# design.net
KiCad netlist of a schematic drawn in EasyEDA Pro
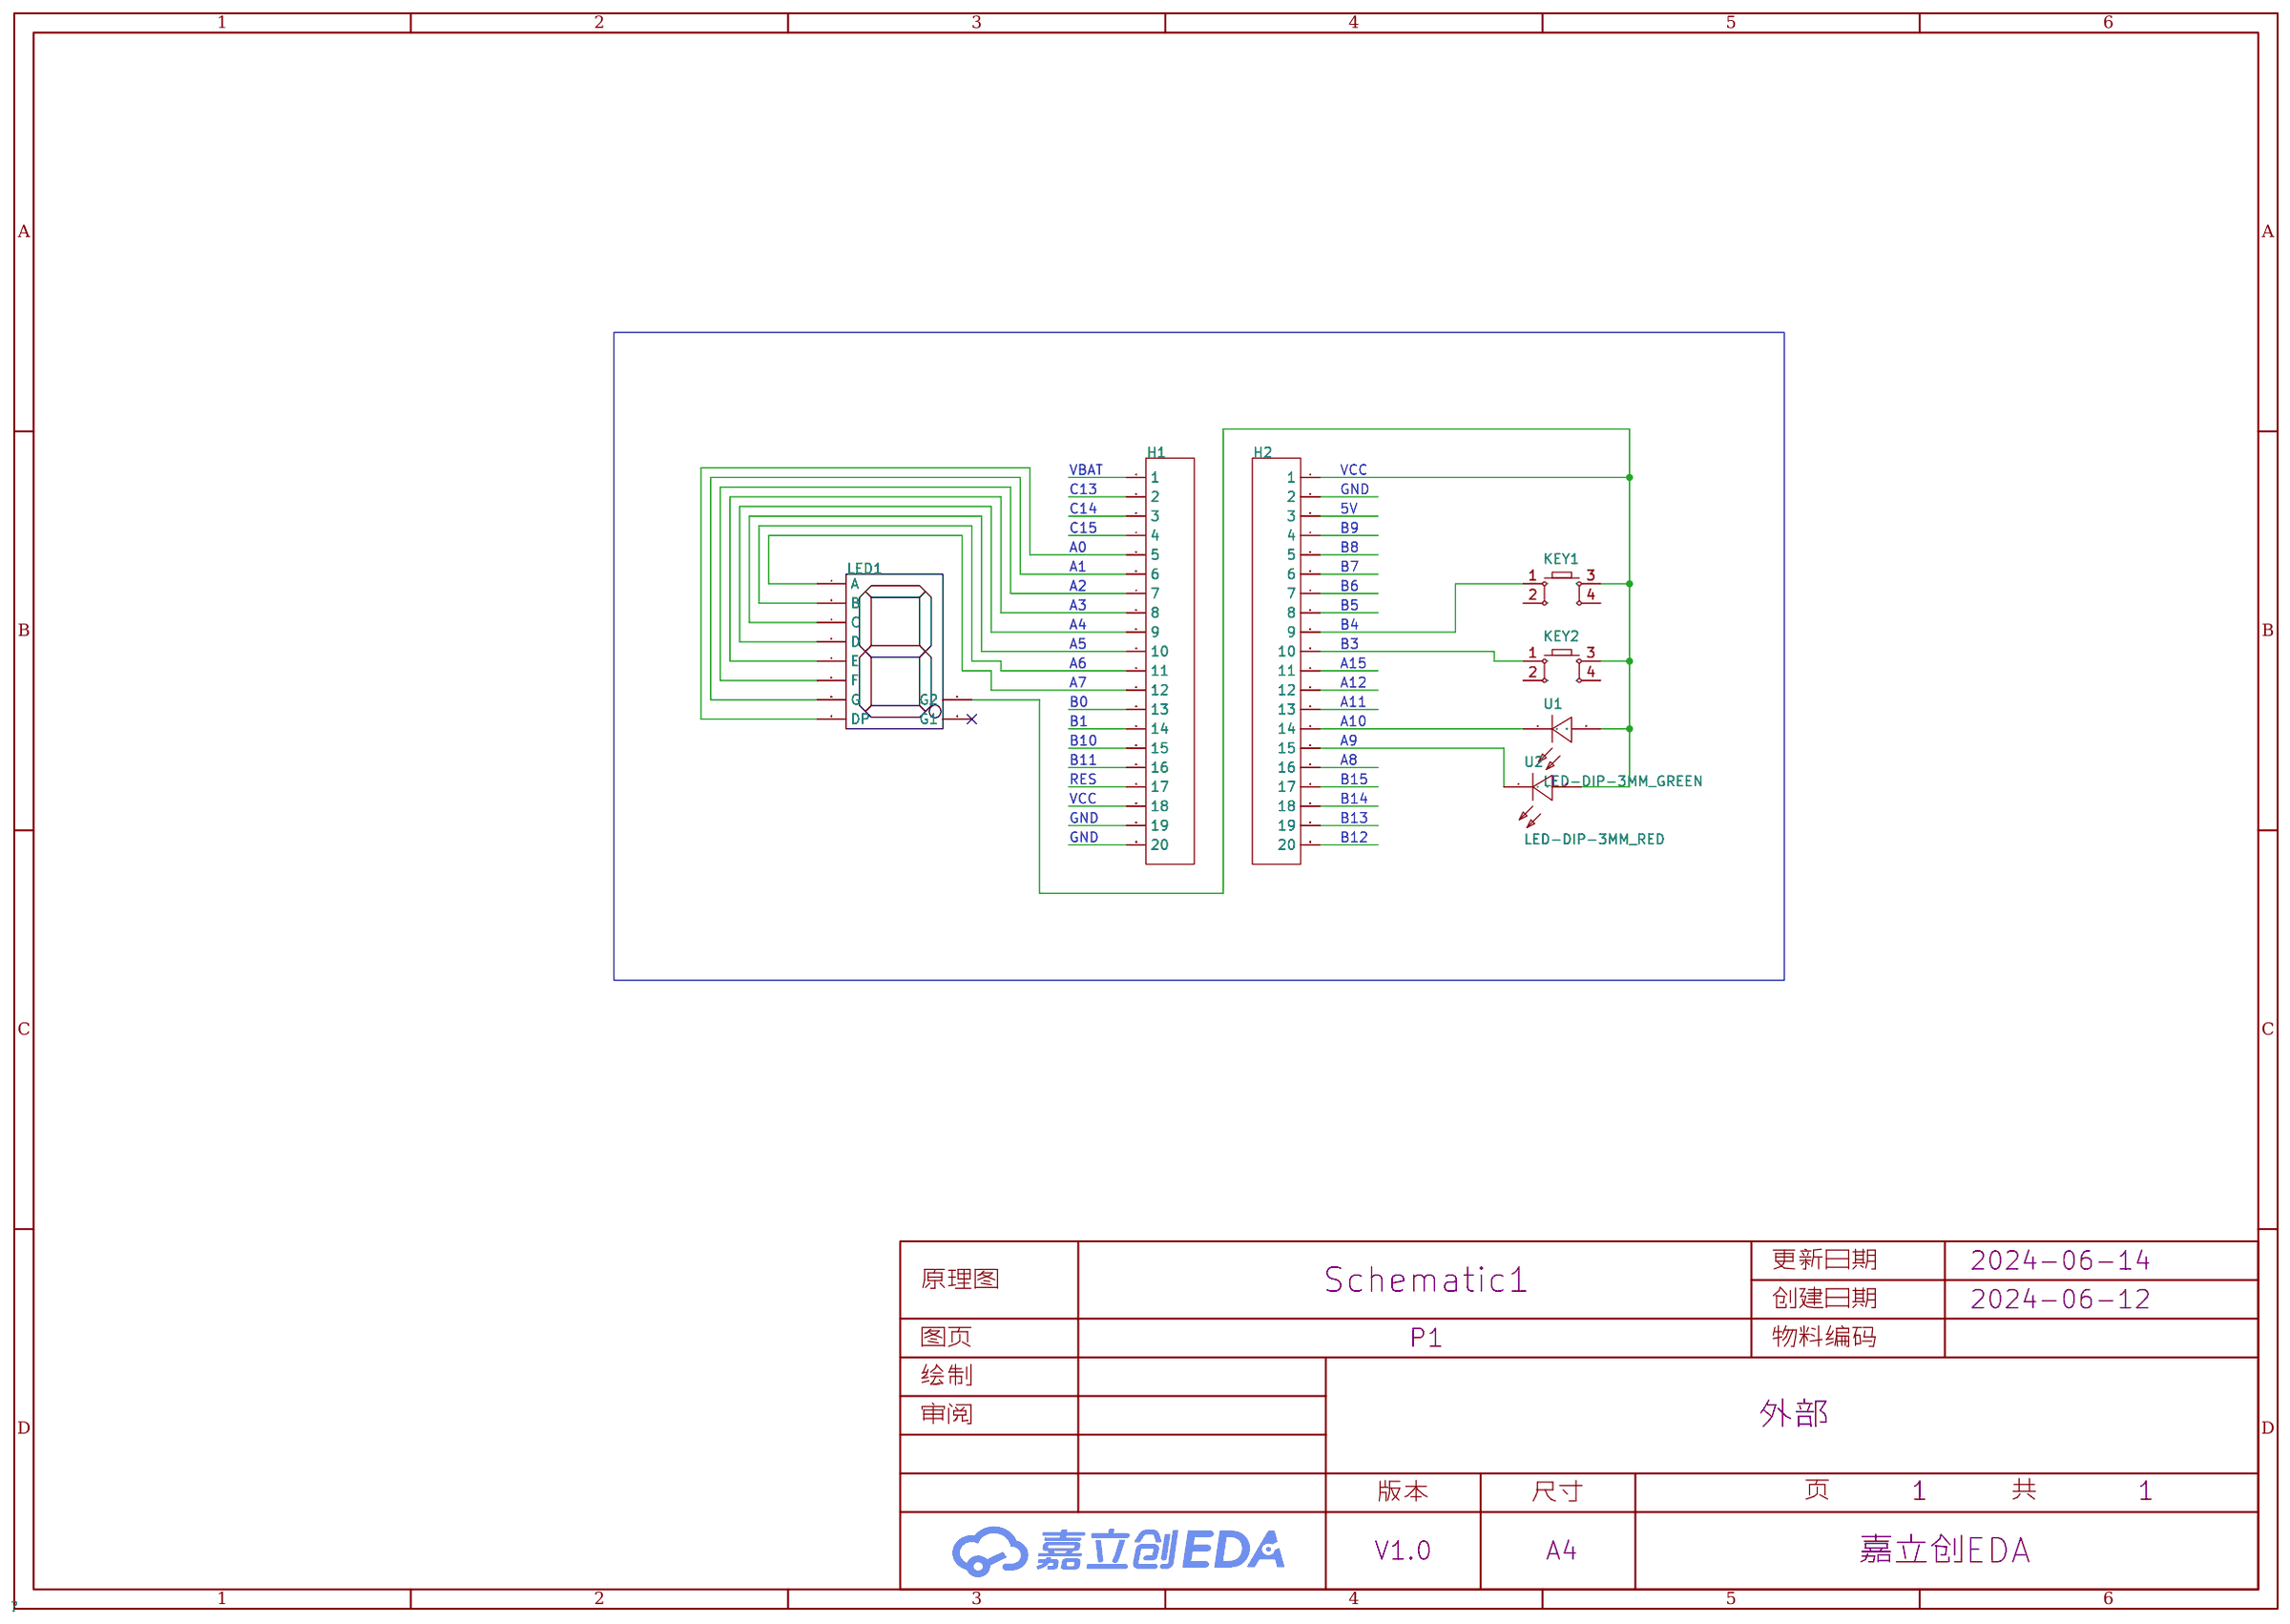
[diagram p0: schematic sheet]

(export (version "E")
  (design (tool "Eeschema 10.0.6"))
  (components
    (comp (ref "H1")
      (value "~")
      (footprint "easyedapro:HDR-TH_20P-P2.54-V-F")
      (libsource (lib "easyedapro") (part "HDR-F_2.54_1x20P"))
    )
    (comp (ref "H2")
      (value "~")
      (footprint "easyedapro:HDR-TH_20P-P2.54-V-F")
      (libsource (lib "easyedapro") (part "HDR-F_2.54_1x20P"))
    )
    (comp (ref "KEY1")
      (value "~")
      (footprint "easyedapro:Key_SMD_12x12x7.3")
      (libsource (lib "easyedapro") (part "轻触按键"))
    )
    (comp (ref "KEY2")
      (value "~")
      (footprint "easyedapro:Key_SMD_12x12x7.3")
      (libsource (lib "easyedapro") (part "轻触按键"))
    )
    (comp (ref "LED1")
      (value "~")
      (footprint "easyedapro:LED-SEG-TH_10P-L12.6-W19.0-P2.54-S15.24-BL")
      (libsource (lib "easyedapro") (part "LED_SEG_TH_0.56*1"))
    )
    (comp (ref "U1")
      (value "LED-DIP-3MM_GREEN")
      (footprint "easyedapro:LED-TH_BD4.0-P2.00-D0.5-RD_BULE")
      (libsource (lib "easyedapro") (part "LED-DIP-3MM_BLUE"))
    )
    (comp (ref "U2")
      (value "LED-DIP-3MM_RED")
      (footprint "easyedapro:LED-TH_BD4.0-P2.00-D0.5-RD_BULE")
      (libsource (lib "easyedapro") (part "LED-DIP-3MM_BLUE"))
    )
  )
  (nets
    (net (code "1") (name "Net-(H2-Pad9)") (class "Default")
      (node (ref "H2") (pin "9") (pinfunction "9_9") (pintype "input"))
      (node (ref "KEY1") (pin "1") (pinfunction "1_1") (pintype "input"))
    )
    (net (code "2") (name "Net-(H2-Pad10)") (class "Default")
      (node (ref "H2") (pin "10") (pinfunction "10_10") (pintype "input"))
      (node (ref "KEY2") (pin "1") (pinfunction "1_1") (pintype "input"))
    )
    (net (code "3") (name "Net-(H2-Pad14)") (class "Default")
      (node (ref "H2") (pin "14") (pinfunction "14_14") (pintype "input"))
      (node (ref "U1") (pin "1") (pinfunction "1_1") (pintype "unspecified"))
    )
    (net (code "4") (name "Net-(H2-Pad15)") (class "Default")
      (node (ref "H2") (pin "15") (pinfunction "15_15") (pintype "input"))
      (node (ref "U2") (pin "1") (pinfunction "1_1") (pintype "unspecified"))
    )
    (net (code "5") (name "Net-(LED1-A)") (class "Default")
      (node (ref "H1") (pin "12") (pinfunction "12_12") (pintype "input"))
      (node (ref "LED1") (pin "7") (pinfunction "A_7") (pintype "input"))
    )
    (net (code "6") (name "Net-(LED1-B)") (class "Default")
      (node (ref "H1") (pin "11") (pinfunction "11_11") (pintype "input"))
      (node (ref "LED1") (pin "6") (pinfunction "B_6") (pintype "input"))
    )
    (net (code "7") (name "Net-(LED1-C)") (class "Default")
      (node (ref "H1") (pin "10") (pinfunction "10_10") (pintype "input"))
      (node (ref "LED1") (pin "4") (pinfunction "C_4") (pintype "input"))
    )
    (net (code "8") (name "Net-(LED1-D)") (class "Default")
      (node (ref "H1") (pin "9") (pinfunction "9_9") (pintype "input"))
      (node (ref "LED1") (pin "2") (pinfunction "D_2") (pintype "input"))
    )
    (net (code "9") (name "Net-(LED1-DP)") (class "Default")
      (node (ref "H1") (pin "5") (pinfunction "5_5") (pintype "input"))
      (node (ref "LED1") (pin "5") (pinfunction "DP_5") (pintype "input"))
    )
    (net (code "10") (name "Net-(LED1-E)") (class "Default")
      (node (ref "H1") (pin "8") (pinfunction "8_8") (pintype "input"))
      (node (ref "LED1") (pin "1") (pinfunction "E_1") (pintype "input"))
    )
    (net (code "11") (name "Net-(LED1-F)") (class "Default")
      (node (ref "H1") (pin "7") (pinfunction "7_7") (pintype "input"))
      (node (ref "LED1") (pin "9") (pinfunction "F_9") (pintype "input"))
    )
    (net (code "12") (name "Net-(LED1-G)") (class "Default")
      (node (ref "H1") (pin "6") (pinfunction "6_6") (pintype "input"))
      (node (ref "LED1") (pin "10") (pinfunction "G_10") (pintype "input"))
    )
    (net (code "13") (name "Net-(LED1-G2)") (class "Default")
      (node (ref "H2") (pin "1") (pinfunction "1_1") (pintype "input"))
      (node (ref "KEY1") (pin "3") (pinfunction "3_3") (pintype "input"))
      (node (ref "KEY2") (pin "3") (pinfunction "3_3") (pintype "input"))
      (node (ref "LED1") (pin "8") (pinfunction "G2_8") (pintype "input"))
      (node (ref "U1") (pin "2") (pinfunction "2_2") (pintype "unspecified"))
      (node (ref "U2") (pin "2") (pinfunction "2_2") (pintype "unspecified"))
    )
    (net (code "14") (name "unconnected-(H1-Pad1)") (class "Default")
      (node (ref "H1") (pin "1") (pinfunction "1_1") (pintype "input"))
    )
    (net (code "15") (name "unconnected-(H1-Pad2)") (class "Default")
      (node (ref "H1") (pin "2") (pinfunction "2_2") (pintype "input"))
    )
    (net (code "16") (name "unconnected-(H1-Pad3)") (class "Default")
      (node (ref "H1") (pin "3") (pinfunction "3_3") (pintype "input"))
    )
    (net (code "17") (name "unconnected-(H1-Pad4)") (class "Default")
      (node (ref "H1") (pin "4") (pinfunction "4_4") (pintype "input"))
    )
    (net (code "18") (name "unconnected-(H1-Pad13)") (class "Default")
      (node (ref "H1") (pin "13") (pinfunction "13_13") (pintype "input"))
    )
    (net (code "19") (name "unconnected-(H1-Pad14)") (class "Default")
      (node (ref "H1") (pin "14") (pinfunction "14_14") (pintype "input"))
    )
    (net (code "20") (name "unconnected-(H1-Pad15)") (class "Default")
      (node (ref "H1") (pin "15") (pinfunction "15_15") (pintype "input"))
    )
    (net (code "21") (name "unconnected-(H1-Pad16)") (class "Default")
      (node (ref "H1") (pin "16") (pinfunction "16_16") (pintype "input"))
    )
    (net (code "22") (name "unconnected-(H1-Pad17)") (class "Default")
      (node (ref "H1") (pin "17") (pinfunction "17_17") (pintype "input"))
    )
    (net (code "23") (name "unconnected-(H1-Pad18)") (class "Default")
      (node (ref "H1") (pin "18") (pinfunction "18_18") (pintype "input"))
    )
    (net (code "24") (name "unconnected-(H1-Pad19)") (class "Default")
      (node (ref "H1") (pin "19") (pinfunction "19_19") (pintype "input"))
    )
    (net (code "25") (name "unconnected-(H1-Pad20)") (class "Default")
      (node (ref "H1") (pin "20") (pinfunction "20_20") (pintype "input"))
    )
    (net (code "26") (name "unconnected-(H2-Pad2)") (class "Default")
      (node (ref "H2") (pin "2") (pinfunction "2_2") (pintype "input"))
    )
    (net (code "27") (name "unconnected-(H2-Pad3)") (class "Default")
      (node (ref "H2") (pin "3") (pinfunction "3_3") (pintype "input"))
    )
    (net (code "28") (name "unconnected-(H2-Pad4)") (class "Default")
      (node (ref "H2") (pin "4") (pinfunction "4_4") (pintype "input"))
    )
    (net (code "29") (name "unconnected-(H2-Pad5)") (class "Default")
      (node (ref "H2") (pin "5") (pinfunction "5_5") (pintype "input"))
    )
    (net (code "30") (name "unconnected-(H2-Pad6)") (class "Default")
      (node (ref "H2") (pin "6") (pinfunction "6_6") (pintype "input"))
    )
    (net (code "31") (name "unconnected-(H2-Pad7)") (class "Default")
      (node (ref "H2") (pin "7") (pinfunction "7_7") (pintype "input"))
    )
    (net (code "32") (name "unconnected-(H2-Pad8)") (class "Default")
      (node (ref "H2") (pin "8") (pinfunction "8_8") (pintype "input"))
    )
    (net (code "33") (name "unconnected-(H2-Pad11)") (class "Default")
      (node (ref "H2") (pin "11") (pinfunction "11_11") (pintype "input"))
    )
    (net (code "34") (name "unconnected-(H2-Pad12)") (class "Default")
      (node (ref "H2") (pin "12") (pinfunction "12_12") (pintype "input"))
    )
    (net (code "35") (name "unconnected-(H2-Pad13)") (class "Default")
      (node (ref "H2") (pin "13") (pinfunction "13_13") (pintype "input"))
    )
    (net (code "36") (name "unconnected-(H2-Pad16)") (class "Default")
      (node (ref "H2") (pin "16") (pinfunction "16_16") (pintype "input"))
    )
    (net (code "37") (name "unconnected-(H2-Pad17)") (class "Default")
      (node (ref "H2") (pin "17") (pinfunction "17_17") (pintype "input"))
    )
    (net (code "38") (name "unconnected-(H2-Pad18)") (class "Default")
      (node (ref "H2") (pin "18") (pinfunction "18_18") (pintype "input"))
    )
    (net (code "39") (name "unconnected-(H2-Pad19)") (class "Default")
      (node (ref "H2") (pin "19") (pinfunction "19_19") (pintype "input"))
    )
    (net (code "40") (name "unconnected-(H2-Pad20)") (class "Default")
      (node (ref "H2") (pin "20") (pinfunction "20_20") (pintype "input"))
    )
    (net (code "41") (name "unconnected-(KEY1-Pad2)") (class "Default")
      (node (ref "KEY1") (pin "2") (pinfunction "2_2") (pintype "input"))
    )
    (net (code "42") (name "unconnected-(KEY1-Pad4)") (class "Default")
      (node (ref "KEY1") (pin "4") (pinfunction "4_4") (pintype "input"))
    )
    (net (code "43") (name "unconnected-(KEY2-Pad2)") (class "Default")
      (node (ref "KEY2") (pin "2") (pinfunction "2_2") (pintype "input"))
    )
    (net (code "44") (name "unconnected-(KEY2-Pad4)") (class "Default")
      (node (ref "KEY2") (pin "4") (pinfunction "4_4") (pintype "input"))
    )
    (net (code "45") (name "unconnected-(LED1-G1-Pad3)") (class "Default")
      (node (ref "LED1") (pin "3") (pinfunction "G1_3") (pintype "input+no_connect"))
    )
  )
)
